# solarInterface.net
KiCad netlist of a schematic drawn in Altium Designer
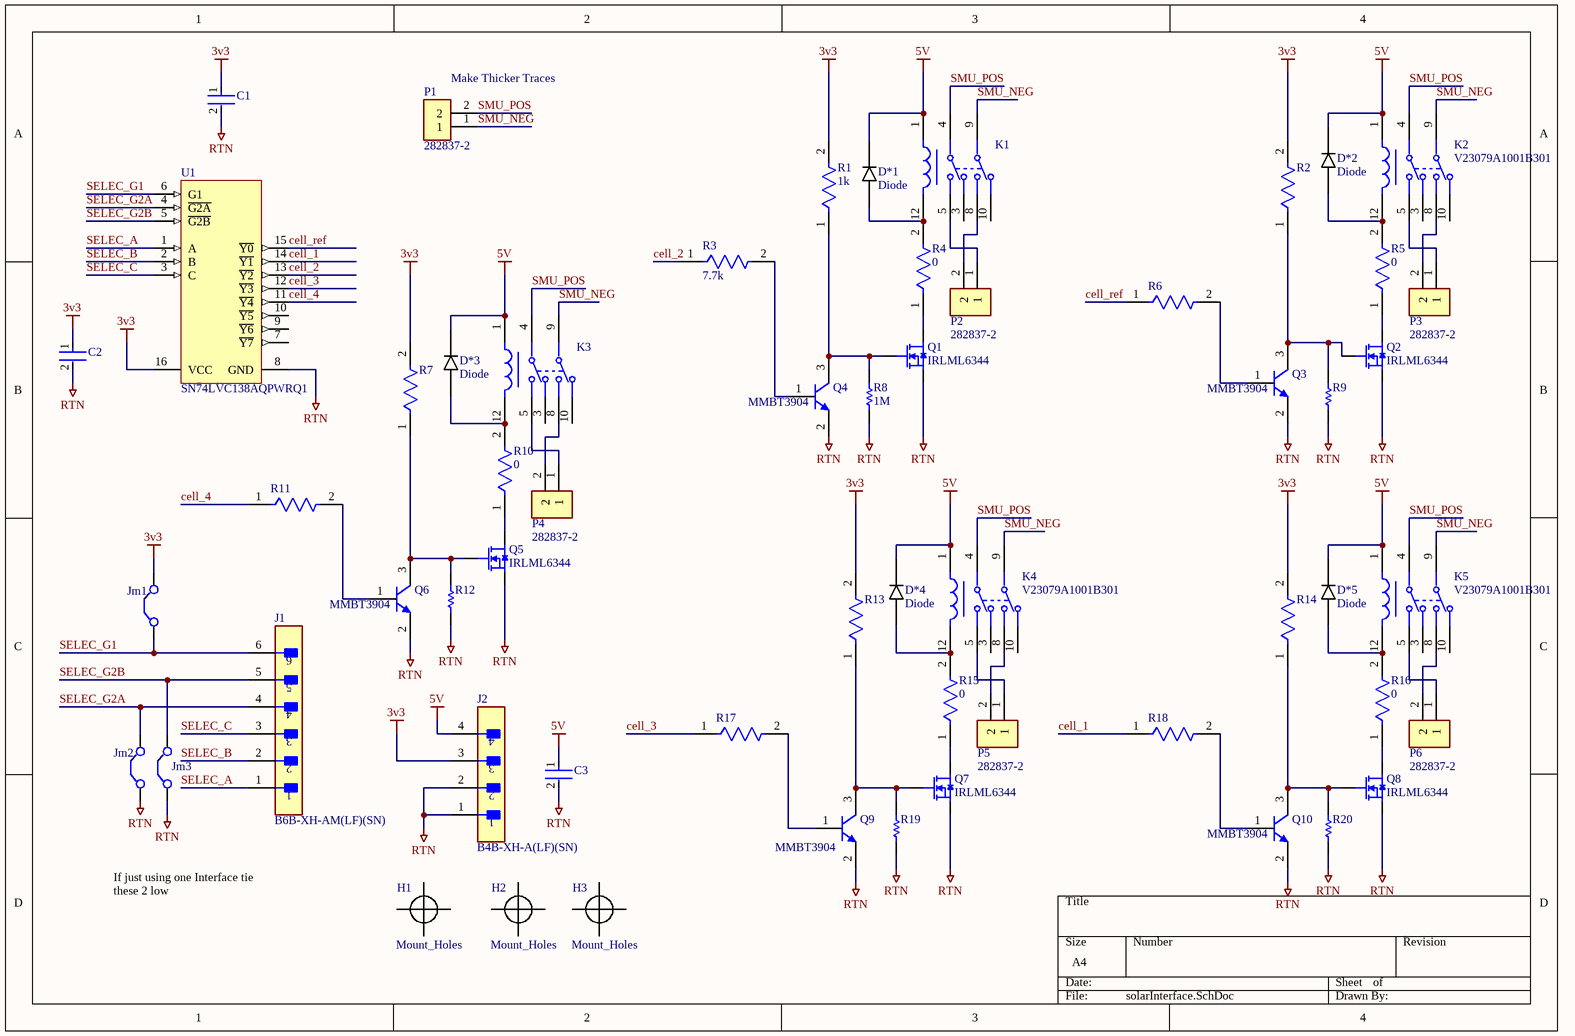
[diagram p0: solarInterface.SchDoc]

(export (version "E")
  (design (tool "Eeschema 10.0.6"))
  (components
    (comp (ref "C1")
      (value "C2012X5R1A336M125AC")
      (footprint "FP-C2012-125-0_2-IPC_A")
      (description "Multilayer Ceramic Capacitors 33μF ±20% 10V X5R SMD 0805")
      (fields (field (name "TOLERANCE") "20%"))
      (libsource (lib "Altium Content Vault") (part "b4654b650e69147ec39a6b967a45e02"))
    )
    (comp (ref "C2")
      (value "C0603X104K5RACTU")
      (footprint "FP-C0603-CJ-MFG")
      (description "CAP CER 0.1UF 50V X7R 0603")
      (fields (field (name "VOLTAGE") "50V") (field (name "MANUFACTURER") "Kemet"))
      (libsource (lib "Altium Content Vault") (part "11868f565c42a9108669ba33697ecf6"))
    )
    (comp (ref "C3")
      (value "GRM188R71C474KA88D")
      (footprint "FP-GRM188-0_1-e0_2_0_5-IPC_A")
      (description "Chip Multilayer Ceramic Capacitors for General Purpose, 0603, 0.47uF, X7R, 15%, 10%, 16V")
      (fields (field (name "VOLTAGE") "16V") (field (name "TOLERANCE") "10%"))
      (libsource (lib "Altium Content Vault") (part "11868f565c42a9108669ba33697ecf6"))
    )
    (comp (ref "D*1")
      (value "Diode")
      (footprint "DIOM6959X26M")
      (libsource (lib "University of Michigan Solar Car Team") (part "Diode"))
    )
    (comp (ref "D*2")
      (value "Diode")
      (footprint "DIOM6959X26M")
      (libsource (lib "University of Michigan Solar Car Team") (part "Diode"))
    )
    (comp (ref "D*3")
      (value "Diode")
      (footprint "DIOM6959X26M")
      (libsource (lib "University of Michigan Solar Car Team") (part "Diode"))
    )
    (comp (ref "D*4")
      (value "Diode")
      (footprint "DIOM6959X26M")
      (libsource (lib "University of Michigan Solar Car Team") (part "Diode"))
    )
    (comp (ref "D*5")
      (value "Diode")
      (footprint "DIOM6959X26M")
      (libsource (lib "University of Michigan Solar Car Team") (part "Diode"))
    )
    (comp (ref "H1")
      (value "Mount_Holes")
      (footprint "MountHole-4-40PTH")
      (libsource (lib "SolarCar") (part "Mount_Holes"))
    )
    (comp (ref "H2")
      (value "Mount_Holes")
      (footprint "MountHole-4-40PTH")
      (libsource (lib "SolarCar") (part "Mount_Holes"))
    )
    (comp (ref "H3")
      (value "Mount_Holes")
      (footprint "MountHole-4-40PTH")
      (libsource (lib "SolarCar") (part "Mount_Holes"))
    )
    (comp (ref "J1")
      (value "B6B-XH-AM(LF)(SN)")
      (footprint "FP-B6B-XH-AM_LF_SN-MFG")
      (description "CONN HEADER VERT 6POS 2.5MM")
      (libsource (lib "Altium Content Vault") (part "f2cb566baf1c37ab5a3b8e90bbeafd6"))
    )
    (comp (ref "J2")
      (value "B4B-XH-A(LF)(SN)")
      (footprint "FP-B4B-XH-A_LF_SN-MFG")
      (description "CONN HEADER VERT 4POS 2.5MM")
      (libsource (lib "Altium Content Vault") (part "299a8cea1bdcbc3624fe62c390fa72c"))
    )
    (comp (ref "Jm1")
      (value "SolderJumper")
      (footprint "bridge")
      (description "Solder Configuration Jumper")
      (fields (field (name "PUBLISHER") "Altium Limited"))
      (libsource (lib "SolarCar") (part "SolderJumper"))
    )
    (comp (ref "Jm2")
      (value "SolderJumper")
      (footprint "bridge")
      (description "Solder Configuration Jumper")
      (fields (field (name "PUBLISHER") "Altium Limited"))
      (libsource (lib "SolarCar") (part "SolderJumper"))
    )
    (comp (ref "Jm3")
      (value "SolderJumper")
      (footprint "bridge")
      (description "Solder Configuration Jumper")
      (fields (field (name "PUBLISHER") "Altium Limited"))
      (libsource (lib "SolarCar") (part "SolderJumper"))
    )
    (comp (ref "K1")
      (value "V23079A1001B301")
      (footprint "FP-V23079A1001B301-MFG")
      (description "RELAY GEN PURPOSE DPDT 2A 5VDC")
      (fields
        (field (name "MANUFACTURER") "TE Connectivity")
        (field (name "OCTOPART") "https://octopart.com/v23079a1001b301-te+connectivity-55433324")
      )
      (libsource (lib "Altium Content Vault") (part "0eb556c25f570307de68544099c8378"))
    )
    (comp (ref "K2")
      (value "V23079A1001B301")
      (footprint "FP-V23079A1001B301-MFG")
      (description "RELAY GEN PURPOSE DPDT 2A 5VDC")
      (fields
        (field (name "MANUFACTURER") "TE Connectivity")
        (field (name "OCTOPART") "https://octopart.com/v23079a1001b301-te+connectivity-55433324")
      )
      (libsource (lib "Altium Content Vault") (part "0eb556c25f570307de68544099c8378"))
    )
    (comp (ref "K3")
      (value "V23079A1001B301")
      (footprint "FP-V23079A1001B301-MFG")
      (description "RELAY GEN PURPOSE DPDT 2A 5VDC")
      (fields
        (field (name "MANUFACTURER") "TE Connectivity")
        (field (name "OCTOPART") "https://octopart.com/v23079a1001b301-te+connectivity-55433324")
      )
      (libsource (lib "Altium Content Vault") (part "0eb556c25f570307de68544099c8378"))
    )
    (comp (ref "K4")
      (value "V23079A1001B301")
      (footprint "FP-V23079A1001B301-MFG")
      (description "RELAY GEN PURPOSE DPDT 2A 5VDC")
      (fields
        (field (name "MANUFACTURER") "TE Connectivity")
        (field (name "OCTOPART") "https://octopart.com/v23079a1001b301-te+connectivity-55433324")
      )
      (libsource (lib "Altium Content Vault") (part "0eb556c25f570307de68544099c8378"))
    )
    (comp (ref "K5")
      (value "V23079A1001B301")
      (footprint "FP-V23079A1001B301-MFG")
      (description "RELAY GEN PURPOSE DPDT 2A 5VDC")
      (fields
        (field (name "MANUFACTURER") "TE Connectivity")
        (field (name "OCTOPART") "https://octopart.com/v23079a1001b301-te+connectivity-55433324")
      )
      (libsource (lib "Altium Content Vault") (part "0eb556c25f570307de68544099c8378"))
    )
    (comp (ref "P1")
      (value "282837-2")
      (footprint "TE_282837-2")
      (fields (field (name "MF") "TE Connectivity"))
      (libsource (lib "") (part "282837-2_1"))
    )
    (comp (ref "P2")
      (value "282837-2")
      (footprint "TE_282837-2")
      (fields (field (name "MF") "TE Connectivity"))
      (libsource (lib "282837-2") (part "282837-2"))
    )
    (comp (ref "P3")
      (value "282837-2")
      (footprint "TE_282837-2")
      (fields (field (name "MF") "TE Connectivity"))
      (libsource (lib "282837-2") (part "282837-2"))
    )
    (comp (ref "P4")
      (value "282837-2")
      (footprint "TE_282837-2")
      (fields (field (name "MF") "TE Connectivity"))
      (libsource (lib "282837-2") (part "282837-2"))
    )
    (comp (ref "P5")
      (value "282837-2")
      (footprint "TE_282837-2")
      (fields (field (name "MF") "TE Connectivity"))
      (libsource (lib "282837-2") (part "282837-2"))
    )
    (comp (ref "P6")
      (value "282837-2")
      (footprint "TE_282837-2")
      (fields (field (name "MF") "TE Connectivity"))
      (libsource (lib "282837-2") (part "282837-2"))
    )
    (comp (ref "Q1")
      (value "IRLML6344")
      (footprint "SOT95P245X110-3N")
      (description "IRLML6344 N MOSFET 5.0A")
      (libsource (lib "University of Michigan Solar Car Team") (part "IRLML6344"))
    )
    (comp (ref "Q2")
      (value "IRLML6344")
      (footprint "SOT95P245X110-3N")
      (description "IRLML6344 N MOSFET 5.0A")
      (libsource (lib "University of Michigan Solar Car Team") (part "IRLML6344"))
    )
    (comp (ref "Q3")
      (value "MMBT3904")
      (footprint "FAIR-SOT23-3_V")
      (description "NPN General Purpose Amplifier, 40 V, 0.2 A, -55 to 150 degC, 3-Pin SOT23, RoHS, Tape and Reel")
      (fields (field (name "MANUFACTURER") "Fairchild Semiconductor") (field (name "POWER") "625mW"))
      (libsource (lib "University of Michigan Solar Car Team") (part "BJT-NPN-BEC-3"))
    )
    (comp (ref "Q4")
      (value "MMBT3904")
      (footprint "FAIR-SOT23-3_V")
      (description "NPN General Purpose Amplifier, 40 V, 0.2 A, -55 to 150 degC, 3-Pin SOT23, RoHS, Tape and Reel")
      (fields (field (name "MANUFACTURER") "Fairchild Semiconductor") (field (name "POWER") "625mW"))
      (libsource (lib "University of Michigan Solar Car Team") (part "BJT-NPN-BEC-3"))
    )
    (comp (ref "Q5")
      (value "IRLML6344")
      (footprint "SOT95P245X110-3N")
      (description "IRLML6344 N MOSFET 5.0A")
      (libsource (lib "University of Michigan Solar Car Team") (part "IRLML6344"))
    )
    (comp (ref "Q6")
      (value "MMBT3904")
      (footprint "FAIR-SOT23-3_V")
      (description "NPN General Purpose Amplifier, 40 V, 0.2 A, -55 to 150 degC, 3-Pin SOT23, RoHS, Tape and Reel")
      (fields (field (name "MANUFACTURER") "Fairchild Semiconductor") (field (name "POWER") "625mW"))
      (libsource (lib "University of Michigan Solar Car Team") (part "BJT-NPN-BEC-3"))
    )
    (comp (ref "Q7")
      (value "IRLML6344")
      (footprint "SOT95P245X110-3N")
      (description "IRLML6344 N MOSFET 5.0A")
      (libsource (lib "University of Michigan Solar Car Team") (part "IRLML6344"))
    )
    (comp (ref "Q8")
      (value "IRLML6344")
      (footprint "SOT95P245X110-3N")
      (description "IRLML6344 N MOSFET 5.0A")
      (libsource (lib "University of Michigan Solar Car Team") (part "IRLML6344"))
    )
    (comp (ref "Q9")
      (value "MMBT3904")
      (footprint "FAIR-SOT23-3_V")
      (description "NPN General Purpose Amplifier, 40 V, 0.2 A, -55 to 150 degC, 3-Pin SOT23, RoHS, Tape and Reel")
      (fields (field (name "MANUFACTURER") "Fairchild Semiconductor") (field (name "POWER") "625mW"))
      (libsource (lib "University of Michigan Solar Car Team") (part "BJT-NPN-BEC-3"))
    )
    (comp (ref "Q10")
      (value "MMBT3904")
      (footprint "FAIR-SOT23-3_V")
      (description "NPN General Purpose Amplifier, 40 V, 0.2 A, -55 to 150 degC, 3-Pin SOT23, RoHS, Tape and Reel")
      (fields (field (name "MANUFACTURER") "Fairchild Semiconductor") (field (name "POWER") "625mW"))
      (libsource (lib "University of Michigan Solar Car Team") (part "BJT-NPN-BEC-3"))
    )
    (comp (ref "R1")
      (value "1k")
      (footprint "FP-RC0603-0_55-IPC_B")
      (description "RES 1K OHM 1% 1/10W 0603\r\nRC0603FR-071KL")
      (fields (field (name "TOLERANCE") "1%"))
      (libsource (lib "Altium Content Vault") (part "1029c3af85768c4190bb7ad29bc67b5"))
    )
    (comp (ref "R2")
      (value "RC0603FR-071KL")
      (footprint "FP-RC0603-0_55-IPC_B")
      (description "RES 1K OHM 1% 1/10W 0603")
      (fields (field (name "TOLERANCE") "1%"))
      (libsource (lib "Altium Content Vault") (part "1029c3af85768c4190bb7ad29bc67b5"))
    )
    (comp (ref "R3")
      (value "7.7k")
      (footprint "FP-RC0603-0_55-IPC_A")
      (description "RES 10K OHM 1% 1/10W 0603\r\nRC0603FR-0710KL")
      (fields (field (name "TOLERANCE") "1%"))
      (libsource (lib "Altium Content Vault") (part "1029c3af85768c4190bb7ad29bc67b5"))
    )
    (comp (ref "R4")
      (value "0")
      (footprint "FP-RC0603-0_55-IPC_B")
      (description "0 OHM 0603")
      (fields (field (name "TOLERANCE") "1%"))
      (libsource (lib "Altium Content Vault") (part "1029c3af85768c4190bb7ad29bc67b5"))
    )
    (comp (ref "R5")
      (value "0")
      (footprint "FP-RC0603-0_55-IPC_B")
      (description "0 OHM 0603")
      (fields (field (name "TOLERANCE") "1%"))
      (libsource (lib "Altium Content Vault") (part "1029c3af85768c4190bb7ad29bc67b5"))
    )
    (comp (ref "R6")
      (value "RC0603FR-0710KL")
      (footprint "FP-RC0603-0_55-IPC_A")
      (description "RES 10K OHM 1% 1/10W 0603")
      (fields (field (name "TOLERANCE") "1%"))
      (libsource (lib "Altium Content Vault") (part "1029c3af85768c4190bb7ad29bc67b5"))
    )
    (comp (ref "R7")
      (value "RC0603FR-071KL")
      (footprint "FP-RC0603-0_55-IPC_B")
      (description "RES 1K OHM 1% 1/10W 0603")
      (fields (field (name "TOLERANCE") "1%"))
      (libsource (lib "Altium Content Vault") (part "1029c3af85768c4190bb7ad29bc67b5"))
    )
    (comp (ref "R8")
      (value "1M")
      (footprint "RESC1608X55X25ML10T15")
      (fields (field (name "TOLERANCE") "20%"))
      (libsource (lib "Altium Content Vault") (part "RES-2"))
    )
    (comp (ref "R9")
      (value "RC0603FR-071ML")
      (footprint "RESC1608X55X25ML10T15")
      (description "Chip Resistor, 1 MOhm, +/- 1%, 100 mW, -55 to 155 degC, 0603 (1608 Metric), RoHS, Tape and Reel")
      (fields (field (name "TOLERANCE") "20%"))
      (libsource (lib "Altium Content Vault") (part "RES-2"))
    )
    (comp (ref "R10")
      (value "0")
      (footprint "FP-RC0603-0_55-IPC_B")
      (description "0 OHM 0603")
      (fields (field (name "TOLERANCE") "1%"))
      (libsource (lib "Altium Content Vault") (part "1029c3af85768c4190bb7ad29bc67b5"))
    )
    (comp (ref "R11")
      (value "RC0603FR-0710KL")
      (footprint "FP-RC0603-0_55-IPC_A")
      (description "RES 10K OHM 1% 1/10W 0603")
      (fields (field (name "TOLERANCE") "1%"))
      (libsource (lib "Altium Content Vault") (part "1029c3af85768c4190bb7ad29bc67b5"))
    )
    (comp (ref "R12")
      (value "RC0603FR-071ML")
      (footprint "RESC1608X55X25ML10T15")
      (description "Chip Resistor, 1 MOhm, +/- 1%, 100 mW, -55 to 155 degC, 0603 (1608 Metric), RoHS, Tape and Reel")
      (fields (field (name "TOLERANCE") "20%"))
      (libsource (lib "Altium Content Vault") (part "RES-2"))
    )
    (comp (ref "R13")
      (value "RC0603FR-071KL")
      (footprint "FP-RC0603-0_55-IPC_B")
      (description "RES 1K OHM 1% 1/10W 0603")
      (fields (field (name "TOLERANCE") "1%"))
      (libsource (lib "Altium Content Vault") (part "1029c3af85768c4190bb7ad29bc67b5"))
    )
    (comp (ref "R14")
      (value "RC0603FR-071KL")
      (footprint "FP-RC0603-0_55-IPC_B")
      (description "RES 1K OHM 1% 1/10W 0603")
      (fields (field (name "TOLERANCE") "1%"))
      (libsource (lib "Altium Content Vault") (part "1029c3af85768c4190bb7ad29bc67b5"))
    )
    (comp (ref "R15")
      (value "0")
      (footprint "FP-RC0603-0_55-IPC_B")
      (description "0 OHM 0603")
      (fields (field (name "TOLERANCE") "1%"))
      (libsource (lib "Altium Content Vault") (part "1029c3af85768c4190bb7ad29bc67b5"))
    )
    (comp (ref "R16")
      (value "0")
      (footprint "FP-RC0603-0_55-IPC_B")
      (description "0 OHM 0603")
      (fields (field (name "TOLERANCE") "1%"))
      (libsource (lib "Altium Content Vault") (part "1029c3af85768c4190bb7ad29bc67b5"))
    )
    (comp (ref "R17")
      (value "RC0603FR-0710KL")
      (footprint "FP-RC0603-0_55-IPC_A")
      (description "RES 10K OHM 1% 1/10W 0603")
      (fields (field (name "TOLERANCE") "1%"))
      (libsource (lib "Altium Content Vault") (part "1029c3af85768c4190bb7ad29bc67b5"))
    )
    (comp (ref "R18")
      (value "RC0603FR-0710KL")
      (footprint "FP-RC0603-0_55-IPC_A")
      (description "RES 10K OHM 1% 1/10W 0603")
      (fields (field (name "TOLERANCE") "1%"))
      (libsource (lib "Altium Content Vault") (part "1029c3af85768c4190bb7ad29bc67b5"))
    )
    (comp (ref "R19")
      (value "RC0603FR-071ML")
      (footprint "RESC1608X55X25ML10T15")
      (description "Chip Resistor, 1 MOhm, +/- 1%, 100 mW, -55 to 155 degC, 0603 (1608 Metric), RoHS, Tape and Reel")
      (fields (field (name "TOLERANCE") "20%"))
      (libsource (lib "Altium Content Vault") (part "RES-2"))
    )
    (comp (ref "R20")
      (value "RC0603FR-071ML")
      (footprint "RESC1608X55X25ML10T15")
      (description "Chip Resistor, 1 MOhm, +/- 1%, 100 mW, -55 to 155 degC, 0603 (1608 Metric), RoHS, Tape and Reel")
      (fields (field (name "TOLERANCE") "20%"))
      (libsource (lib "Altium Content Vault") (part "RES-2"))
    )
    (comp (ref "U1")
      (value "SN74LVC138AQPWRQ1")
      (footprint "PW0016A_M")
      (description "Automotive Catalog 3-Line To 8-Line decoder/Demultiplexer, PW0016A, LARGE T&R")
      (fields
        (field (name "MANUFACTURER") "Texas Instruments")
        (field (name "GENERIC PART NUMBER") "SN74LVC138A-Q1")
      )
      (libsource (lib "Altium Content Vault") (part "TI-SN54_74XXX138X-16"))
    )
  )
  (nets
    (net (code "1") (name "/SELEC_A") (class "Default")
      (node (ref "J1") (pin "1") (pinfunction "1_1") (pintype "passive"))
      (node (ref "U1") (pin "1") (pinfunction "A_1") (pintype "input"))
    )
    (net (code "2") (name "/SELEC_B") (class "Default")
      (node (ref "J1") (pin "2") (pinfunction "2_2") (pintype "passive"))
      (node (ref "U1") (pin "2") (pinfunction "B_2") (pintype "input"))
    )
    (net (code "3") (name "/SELEC_C") (class "Default")
      (node (ref "J1") (pin "3") (pinfunction "3_3") (pintype "passive"))
      (node (ref "U1") (pin "3") (pinfunction "C_3") (pintype "input"))
    )
    (net (code "4") (name "/SELEC_G1") (class "Default")
      (node (ref "J1") (pin "6") (pinfunction "6_6") (pintype "passive"))
      (node (ref "Jm1") (pin "1") (pinfunction "C1_1") (pintype "passive"))
      (node (ref "U1") (pin "6") (pinfunction "G1_6") (pintype "input"))
    )
    (net (code "5") (name "/SELEC_G2A") (class "Default")
      (node (ref "J1") (pin "4") (pinfunction "4_4") (pintype "passive"))
      (node (ref "Jm2") (pin "2") (pinfunction "C2_2") (pintype "passive"))
      (node (ref "U1") (pin "4") (pinfunction "~{G2A}_4") (pintype "input"))
    )
    (net (code "6") (name "/SELEC_G2B") (class "Default")
      (node (ref "J1") (pin "5") (pinfunction "5_5") (pintype "passive"))
      (node (ref "Jm3") (pin "2") (pinfunction "C2_2") (pintype "passive"))
      (node (ref "U1") (pin "5") (pinfunction "~{G2B}_5") (pintype "input"))
    )
    (net (code "7") (name "/SMU_NEG") (class "Default")
      (node (ref "K1") (pin "9") (pinfunction "9_9") (pintype "passive"))
      (node (ref "K2") (pin "9") (pinfunction "9_9") (pintype "passive"))
      (node (ref "K3") (pin "9") (pinfunction "9_9") (pintype "passive"))
      (node (ref "K4") (pin "9") (pinfunction "9_9") (pintype "passive"))
      (node (ref "K5") (pin "9") (pinfunction "9_9") (pintype "passive"))
      (node (ref "P1") (pin "1") (pinfunction "1_1") (pintype "passive"))
    )
    (net (code "8") (name "/SMU_POS") (class "Default")
      (node (ref "K1") (pin "4") (pinfunction "4_4") (pintype "passive"))
      (node (ref "K2") (pin "4") (pinfunction "4_4") (pintype "passive"))
      (node (ref "K3") (pin "4") (pinfunction "4_4") (pintype "passive"))
      (node (ref "K4") (pin "4") (pinfunction "4_4") (pintype "passive"))
      (node (ref "K5") (pin "4") (pinfunction "4_4") (pintype "passive"))
      (node (ref "P1") (pin "2") (pinfunction "2_2") (pintype "passive"))
    )
    (net (code "9") (name "/cell_1") (class "Default")
      (node (ref "R18") (pin "1") (pinfunction "1_1") (pintype "passive"))
      (node (ref "U1") (pin "14") (pinfunction "~{Y1}_14") (pintype "output"))
    )
    (net (code "10") (name "/cell_2") (class "Default")
      (node (ref "R3") (pin "1") (pinfunction "1_1") (pintype "passive"))
      (node (ref "U1") (pin "13") (pinfunction "~{Y2}_13") (pintype "output"))
    )
    (net (code "11") (name "/cell_3") (class "Default")
      (node (ref "R17") (pin "1") (pinfunction "1_1") (pintype "passive"))
      (node (ref "U1") (pin "12") (pinfunction "~{Y3}_12") (pintype "output"))
    )
    (net (code "12") (name "/cell_4") (class "Default")
      (node (ref "R11") (pin "1") (pinfunction "1_1") (pintype "passive"))
      (node (ref "U1") (pin "11") (pinfunction "~{Y4}_11") (pintype "output"))
    )
    (net (code "13") (name "/cell_ref") (class "Default")
      (node (ref "R6") (pin "1") (pinfunction "1_1") (pintype "passive"))
      (node (ref "U1") (pin "15") (pinfunction "~{Y0}_15") (pintype "output"))
    )
    (net (code "14") (name "3v3") (class "Default")
      (node (ref "C1") (pin "1") (pinfunction "1_1") (pintype "passive"))
      (node (ref "C2") (pin "1") (pinfunction "1_1") (pintype "passive"))
      (node (ref "J2") (pin "3") (pinfunction "3_3") (pintype "passive"))
      (node (ref "Jm1") (pin "2") (pinfunction "C2_2") (pintype "passive"))
      (node (ref "R1") (pin "2") (pinfunction "2_2") (pintype "passive"))
      (node (ref "R13") (pin "2") (pinfunction "2_2") (pintype "passive"))
      (node (ref "R14") (pin "2") (pinfunction "2_2") (pintype "passive"))
      (node (ref "R2") (pin "2") (pinfunction "2_2") (pintype "passive"))
      (node (ref "R7") (pin "2") (pinfunction "2_2") (pintype "passive"))
      (node (ref "U1") (pin "16") (pinfunction "VCC_16") (pintype "power_in"))
    )
    (net (code "15") (name "5V") (class "Default")
      (node (ref "C3") (pin "1") (pinfunction "1_1") (pintype "passive"))
      (node (ref "D*1") (pin "CAT") (pinfunction "CAT_CAT") (pintype "power_in"))
      (node (ref "D*2") (pin "CAT") (pinfunction "CAT_CAT") (pintype "power_in"))
      (node (ref "D*3") (pin "CAT") (pinfunction "CAT_CAT") (pintype "power_in"))
      (node (ref "D*4") (pin "CAT") (pinfunction "CAT_CAT") (pintype "power_in"))
      (node (ref "D*5") (pin "CAT") (pinfunction "CAT_CAT") (pintype "power_in"))
      (node (ref "J2") (pin "4") (pinfunction "4_4") (pintype "passive"))
      (node (ref "K1") (pin "1") (pinfunction "1_1") (pintype "passive"))
      (node (ref "K2") (pin "1") (pinfunction "1_1") (pintype "passive"))
      (node (ref "K3") (pin "1") (pinfunction "1_1") (pintype "passive"))
      (node (ref "K4") (pin "1") (pinfunction "1_1") (pintype "passive"))
      (node (ref "K5") (pin "1") (pinfunction "1_1") (pintype "passive"))
    )
    (net (code "16") (name "Net-(D*1-PadAN)") (class "Default")
      (node (ref "D*1") (pin "AN") (pinfunction "AN_AN") (pintype "power_in"))
      (node (ref "K1") (pin "12") (pinfunction "12_12") (pintype "passive"))
      (node (ref "R4") (pin "2") (pinfunction "2_2") (pintype "passive"))
    )
    (net (code "17") (name "Net-(D*2-PadAN)") (class "Default")
      (node (ref "D*2") (pin "AN") (pinfunction "AN_AN") (pintype "power_in"))
      (node (ref "K2") (pin "12") (pinfunction "12_12") (pintype "passive"))
      (node (ref "R5") (pin "2") (pinfunction "2_2") (pintype "passive"))
    )
    (net (code "18") (name "Net-(D*3-PadAN)") (class "Default")
      (node (ref "D*3") (pin "AN") (pinfunction "AN_AN") (pintype "power_in"))
      (node (ref "K3") (pin "12") (pinfunction "12_12") (pintype "passive"))
      (node (ref "R10") (pin "2") (pinfunction "2_2") (pintype "passive"))
    )
    (net (code "19") (name "Net-(D*4-PadAN)") (class "Default")
      (node (ref "D*4") (pin "AN") (pinfunction "AN_AN") (pintype "power_in"))
      (node (ref "K4") (pin "12") (pinfunction "12_12") (pintype "passive"))
      (node (ref "R15") (pin "2") (pinfunction "2_2") (pintype "passive"))
    )
    (net (code "20") (name "Net-(D*5-PadAN)") (class "Default")
      (node (ref "D*5") (pin "AN") (pinfunction "AN_AN") (pintype "power_in"))
      (node (ref "K5") (pin "12") (pinfunction "12_12") (pintype "passive"))
      (node (ref "R16") (pin "2") (pinfunction "2_2") (pintype "passive"))
    )
    (net (code "21") (name "Net-(K1-Pad5)") (class "Default")
      (node (ref "K1") (pin "5") (pinfunction "5_5") (pintype "passive"))
      (node (ref "P2") (pin "1") (pinfunction "1_1") (pintype "passive"))
    )
    (net (code "22") (name "Net-(K1-Pad8)") (class "Default")
      (node (ref "K1") (pin "8") (pinfunction "8_8") (pintype "passive"))
      (node (ref "P2") (pin "2") (pinfunction "2_2") (pintype "passive"))
    )
    (net (code "23") (name "Net-(K2-Pad5)") (class "Default")
      (node (ref "K2") (pin "5") (pinfunction "5_5") (pintype "passive"))
      (node (ref "P3") (pin "1") (pinfunction "1_1") (pintype "passive"))
    )
    (net (code "24") (name "Net-(K2-Pad8)") (class "Default")
      (node (ref "K2") (pin "8") (pinfunction "8_8") (pintype "passive"))
      (node (ref "P3") (pin "2") (pinfunction "2_2") (pintype "passive"))
    )
    (net (code "25") (name "Net-(K3-Pad5)") (class "Default")
      (node (ref "K3") (pin "5") (pinfunction "5_5") (pintype "passive"))
      (node (ref "P4") (pin "1") (pinfunction "1_1") (pintype "passive"))
    )
    (net (code "26") (name "Net-(K3-Pad8)") (class "Default")
      (node (ref "K3") (pin "8") (pinfunction "8_8") (pintype "passive"))
      (node (ref "P4") (pin "2") (pinfunction "2_2") (pintype "passive"))
    )
    (net (code "27") (name "Net-(K4-Pad5)") (class "Default")
      (node (ref "K4") (pin "5") (pinfunction "5_5") (pintype "passive"))
      (node (ref "P5") (pin "1") (pinfunction "1_1") (pintype "passive"))
    )
    (net (code "28") (name "Net-(K4-Pad8)") (class "Default")
      (node (ref "K4") (pin "8") (pinfunction "8_8") (pintype "passive"))
      (node (ref "P5") (pin "2") (pinfunction "2_2") (pintype "passive"))
    )
    (net (code "29") (name "Net-(K5-Pad5)") (class "Default")
      (node (ref "K5") (pin "5") (pinfunction "5_5") (pintype "passive"))
      (node (ref "P6") (pin "1") (pinfunction "1_1") (pintype "passive"))
    )
    (net (code "30") (name "Net-(K5-Pad8)") (class "Default")
      (node (ref "K5") (pin "8") (pinfunction "8_8") (pintype "passive"))
      (node (ref "P6") (pin "2") (pinfunction "2_2") (pintype "passive"))
    )
    (net (code "31") (name "Net-(Q1-D)") (class "Default")
      (node (ref "Q1") (pin "3") (pinfunction "D_3") (pintype "passive"))
      (node (ref "R4") (pin "1") (pinfunction "1_1") (pintype "passive"))
    )
    (net (code "32") (name "Net-(Q1-G)") (class "Default")
      (node (ref "Q1") (pin "1") (pinfunction "G_1") (pintype "passive"))
      (node (ref "Q4") (pin "3") (pinfunction "C_3") (pintype "passive"))
      (node (ref "R1") (pin "1") (pinfunction "1_1") (pintype "passive"))
      (node (ref "R8") (pin "2") (pinfunction "2_2") (pintype "passive"))
    )
    (net (code "33") (name "Net-(Q2-D)") (class "Default")
      (node (ref "Q2") (pin "3") (pinfunction "D_3") (pintype "passive"))
      (node (ref "R5") (pin "1") (pinfunction "1_1") (pintype "passive"))
    )
    (net (code "34") (name "Net-(Q2-G)") (class "Default")
      (node (ref "Q2") (pin "1") (pinfunction "G_1") (pintype "passive"))
      (node (ref "Q3") (pin "3") (pinfunction "C_3") (pintype "passive"))
      (node (ref "R2") (pin "1") (pinfunction "1_1") (pintype "passive"))
      (node (ref "R9") (pin "2") (pinfunction "2_2") (pintype "passive"))
    )
    (net (code "35") (name "Net-(Q3-B)") (class "Default")
      (node (ref "Q3") (pin "1") (pinfunction "B_1") (pintype "passive"))
      (node (ref "R6") (pin "2") (pinfunction "2_2") (pintype "passive"))
    )
    (net (code "36") (name "Net-(Q4-B)") (class "Default")
      (node (ref "Q4") (pin "1") (pinfunction "B_1") (pintype "passive"))
      (node (ref "R3") (pin "2") (pinfunction "2_2") (pintype "passive"))
    )
    (net (code "37") (name "Net-(Q5-D)") (class "Default")
      (node (ref "Q5") (pin "3") (pinfunction "D_3") (pintype "passive"))
      (node (ref "R10") (pin "1") (pinfunction "1_1") (pintype "passive"))
    )
    (net (code "38") (name "Net-(Q5-G)") (class "Default")
      (node (ref "Q5") (pin "1") (pinfunction "G_1") (pintype "passive"))
      (node (ref "Q6") (pin "3") (pinfunction "C_3") (pintype "passive"))
      (node (ref "R12") (pin "2") (pinfunction "2_2") (pintype "passive"))
      (node (ref "R7") (pin "1") (pinfunction "1_1") (pintype "passive"))
    )
    (net (code "39") (name "Net-(Q6-B)") (class "Default")
      (node (ref "Q6") (pin "1") (pinfunction "B_1") (pintype "passive"))
      (node (ref "R11") (pin "2") (pinfunction "2_2") (pintype "passive"))
    )
    (net (code "40") (name "Net-(Q7-D)") (class "Default")
      (node (ref "Q7") (pin "3") (pinfunction "D_3") (pintype "passive"))
      (node (ref "R15") (pin "1") (pinfunction "1_1") (pintype "passive"))
    )
    (net (code "41") (name "Net-(Q7-G)") (class "Default")
      (node (ref "Q7") (pin "1") (pinfunction "G_1") (pintype "passive"))
      (node (ref "Q9") (pin "3") (pinfunction "C_3") (pintype "passive"))
      (node (ref "R13") (pin "1") (pinfunction "1_1") (pintype "passive"))
      (node (ref "R19") (pin "2") (pinfunction "2_2") (pintype "passive"))
    )
    (net (code "42") (name "Net-(Q8-D)") (class "Default")
      (node (ref "Q8") (pin "3") (pinfunction "D_3") (pintype "passive"))
      (node (ref "R16") (pin "1") (pinfunction "1_1") (pintype "passive"))
    )
    (net (code "43") (name "Net-(Q9-B)") (class "Default")
      (node (ref "Q9") (pin "1") (pinfunction "B_1") (pintype "passive"))
      (node (ref "R17") (pin "2") (pinfunction "2_2") (pintype "passive"))
    )
    (net (code "44") (name "Net-(Q10-B)") (class "Default")
      (node (ref "Q10") (pin "1") (pinfunction "B_1") (pintype "passive"))
      (node (ref "R18") (pin "2") (pinfunction "2_2") (pintype "passive"))
    )
    (net (code "45") (name "Net-(Q10-C)") (class "Default")
      (node (ref "Q10") (pin "3") (pinfunction "C_3") (pintype "passive"))
      (node (ref "Q8") (pin "1") (pinfunction "G_1") (pintype "passive"))
      (node (ref "R14") (pin "1") (pinfunction "1_1") (pintype "passive"))
      (node (ref "R20") (pin "2") (pinfunction "2_2") (pintype "passive"))
    )
    (net (code "46") (name "RTN") (class "Default")
      (node (ref "C1") (pin "2") (pinfunction "2_2") (pintype "passive"))
      (node (ref "C2") (pin "2") (pinfunction "2_2") (pintype "passive"))
      (node (ref "C3") (pin "2") (pinfunction "2_2") (pintype "passive"))
      (node (ref "J2") (pin "1") (pinfunction "1_1") (pintype "passive"))
      (node (ref "J2") (pin "2") (pinfunction "2_2") (pintype "passive"))
      (node (ref "Jm2") (pin "1") (pinfunction "C1_1") (pintype "passive"))
      (node (ref "Jm3") (pin "1") (pinfunction "C1_1") (pintype "passive"))
      (node (ref "Q1") (pin "2") (pinfunction "S_2") (pintype "passive"))
      (node (ref "Q10") (pin "2") (pinfunction "E_2") (pintype "passive"))
      (node (ref "Q2") (pin "2") (pinfunction "S_2") (pintype "passive"))
      (node (ref "Q3") (pin "2") (pinfunction "E_2") (pintype "passive"))
      (node (ref "Q4") (pin "2") (pinfunction "E_2") (pintype "passive"))
      (node (ref "Q5") (pin "2") (pinfunction "S_2") (pintype "passive"))
      (node (ref "Q6") (pin "2") (pinfunction "E_2") (pintype "passive"))
      (node (ref "Q7") (pin "2") (pinfunction "S_2") (pintype "passive"))
      (node (ref "Q8") (pin "2") (pinfunction "S_2") (pintype "passive"))
      (node (ref "Q9") (pin "2") (pinfunction "E_2") (pintype "passive"))
      (node (ref "R12") (pin "1") (pinfunction "1_1") (pintype "passive"))
      (node (ref "R19") (pin "1") (pinfunction "1_1") (pintype "passive"))
      (node (ref "R20") (pin "1") (pinfunction "1_1") (pintype "passive"))
      (node (ref "R8") (pin "1") (pinfunction "1_1") (pintype "passive"))
      (node (ref "R9") (pin "1") (pinfunction "1_1") (pintype "passive"))
      (node (ref "U1") (pin "8") (pinfunction "GND_8") (pintype "power_in"))
    )
    (net (code "47") (name "unconnected-(H1-Pad0)") (class "Default")
      (node (ref "H1") (pin "0") (pinfunction "0_0") (pintype "passive"))
    )
    (net (code "48") (name "unconnected-(H2-Pad0)") (class "Default")
      (node (ref "H2") (pin "0") (pinfunction "0_0") (pintype "passive"))
    )
    (net (code "49") (name "unconnected-(H3-Pad0)") (class "Default")
      (node (ref "H3") (pin "0") (pinfunction "0_0") (pintype "passive"))
    )
    (net (code "50") (name "unconnected-(K1-Pad3)") (class "Default")
      (node (ref "K1") (pin "3") (pinfunction "3_3") (pintype "passive"))
    )
    (net (code "51") (name "unconnected-(K1-Pad10)") (class "Default")
      (node (ref "K1") (pin "10") (pinfunction "10_10") (pintype "passive"))
    )
    (net (code "52") (name "unconnected-(K2-Pad3)") (class "Default")
      (node (ref "K2") (pin "3") (pinfunction "3_3") (pintype "passive"))
    )
    (net (code "53") (name "unconnected-(K2-Pad10)") (class "Default")
      (node (ref "K2") (pin "10") (pinfunction "10_10") (pintype "passive"))
    )
    (net (code "54") (name "unconnected-(K3-Pad3)") (class "Default")
      (node (ref "K3") (pin "3") (pinfunction "3_3") (pintype "passive"))
    )
    (net (code "55") (name "unconnected-(K3-Pad10)") (class "Default")
      (node (ref "K3") (pin "10") (pinfunction "10_10") (pintype "passive"))
    )
    (net (code "56") (name "unconnected-(K4-Pad3)") (class "Default")
      (node (ref "K4") (pin "3") (pinfunction "3_3") (pintype "passive"))
    )
    (net (code "57") (name "unconnected-(K4-Pad10)") (class "Default")
      (node (ref "K4") (pin "10") (pinfunction "10_10") (pintype "passive"))
    )
    (net (code "58") (name "unconnected-(K5-Pad3)") (class "Default")
      (node (ref "K5") (pin "3") (pinfunction "3_3") (pintype "passive"))
    )
    (net (code "59") (name "unconnected-(K5-Pad10)") (class "Default")
      (node (ref "K5") (pin "10") (pinfunction "10_10") (pintype "passive"))
    )
    (net (code "60") (name "unconnected-(U1-~{Y5}-Pad10)") (class "Default")
      (node (ref "U1") (pin "10") (pinfunction "~{Y5}_10") (pintype "output"))
    )
    (net (code "61") (name "unconnected-(U1-~{Y6}-Pad9)") (class "Default")
      (node (ref "U1") (pin "9") (pinfunction "~{Y6}_9") (pintype "output"))
    )
    (net (code "62") (name "unconnected-(U1-~{Y7}-Pad7)") (class "Default")
      (node (ref "U1") (pin "7") (pinfunction "~{Y7}_7") (pintype "output"))
    )
  )
)
